# light_switch_smd.net
KiCad netlist of a schematic drawn in EAGLE
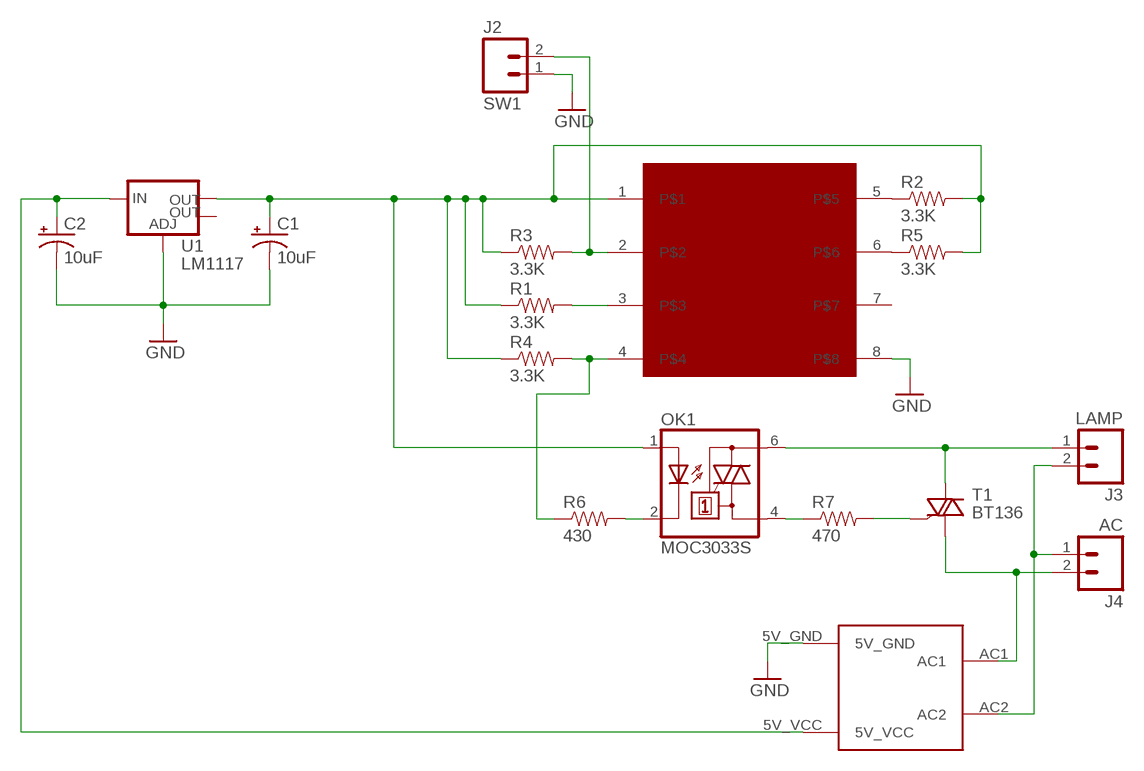
[diagram p0: schematic, sheet 1]

(export (version "E")
  (design (tool "Eeschema 10.0.6"))
  (components
    (comp (ref "C1")
      (value "10uF")
      (footprint "eagle-import:EIA3216")
      (libsource (lib "eagle-import") (part "10UF-16V-10%(TANT)"))
    )
    (comp (ref "C2")
      (value "10uF")
      (footprint "eagle-import:EIA3216")
      (libsource (lib "eagle-import") (part "10UF-16V-10%(TANT)"))
    )
    (comp (ref "J2")
      (value "SW1")
      (footprint "eagle-import:1X02_LONGPADS")
      (libsource (lib "eagle-import") (part "M02PTH3"))
    )
    (comp (ref "J3")
      (value "LAMP")
      (footprint "eagle-import:JST-2-PTH-VERT")
      (libsource (lib "eagle-import") (part "M02JST-PTH-VERT"))
    )
    (comp (ref "J4")
      (value "AC")
      (footprint "eagle-import:JST-2-PTH-VERT")
      (libsource (lib "eagle-import") (part "M02JST-PTH-VERT"))
    )
    (comp (ref "OK1")
      (value "MOC3033S")
      (footprint "eagle-import:DIL6-SMD")
      (fields (field (name "MF") "FAIRCHILD SEMICONDUCTOR") (field (name "MPN") "MOC3033S-M"))
      (libsource (lib "eagle-import") (part "MOC30S33"))
    )
    (comp (ref "R1")
      (value "3.3K")
      (footprint "eagle-import:1206")
      (libsource (lib "eagle-import") (part "RESISTOR1206"))
    )
    (comp (ref "R2")
      (value "3.3K")
      (footprint "eagle-import:1206")
      (libsource (lib "eagle-import") (part "RESISTOR1206"))
    )
    (comp (ref "R3")
      (value "3.3K")
      (footprint "eagle-import:1206")
      (libsource (lib "eagle-import") (part "RESISTOR1206"))
    )
    (comp (ref "R4")
      (value "3.3K")
      (footprint "eagle-import:1206")
      (libsource (lib "eagle-import") (part "RESISTOR1206"))
    )
    (comp (ref "R5")
      (value "3.3K")
      (footprint "eagle-import:1206")
      (libsource (lib "eagle-import") (part "RESISTOR1206"))
    )
    (comp (ref "R6")
      (value "430")
      (footprint "eagle-import:1206")
      (libsource (lib "eagle-import") (part "RESISTOR1206"))
    )
    (comp (ref "R7")
      (value "470")
      (footprint "eagle-import:1206")
      (libsource (lib "eagle-import") (part "RESISTOR1206"))
    )
    (comp (ref "T1")
      (value "BT136")
      (footprint "eagle-import:TO220AB")
      (libsource (lib "eagle-import") (part "BT136"))
    )
    (comp (ref "U$1")
      (value "HI-LINK5V-ACDC")
      (footprint "eagle-import:AC5V")
      (libsource (lib "eagle-import") (part "HI-LINK5V-ACDC"))
    )
    (comp (ref "U$2")
      (value "ESP8266-01")
      (footprint "eagle-import:ESP8266-01")
      (libsource (lib "eagle-import") (part "ESP8266-01"))
    )
    (comp (ref "U1")
      (value "LM1117")
      (footprint "eagle-import:SOT223")
      (libsource (lib "eagle-import") (part "V_REG_LM1117SOT223"))
    )
  )
  (nets
    (net (code "1") (name "GND") (class "Default")
      (node (ref "C1") (pin "C") (pinfunction "-_C") (pintype "passive"))
      (node (ref "C2") (pin "C") (pinfunction "-_C") (pintype "passive"))
      (node (ref "J2") (pin "1") (pinfunction "1_1") (pintype "passive"))
      (node (ref "U$1") (pin "5V_GND") (pinfunction "5V_GND_5V_GND") (pintype "bidirectional"))
      (node (ref "U$2") (pin "8") (pinfunction "P$8_8") (pintype "bidirectional"))
      (node (ref "U1") (pin "1") (pinfunction "ADJ_1") (pintype "input"))
    )
    (net (code "2") (name "Net-(C1-+)") (class "Default")
      (node (ref "C1") (pin "A") (pinfunction "+_A") (pintype "passive"))
      (node (ref "OK1") (pin "1") (pinfunction "A_1") (pintype "passive"))
      (node (ref "R1") (pin "1") (pinfunction "1_1") (pintype "passive"))
      (node (ref "R2") (pin "2") (pinfunction "2_2") (pintype "passive"))
      (node (ref "R3") (pin "1") (pinfunction "1_1") (pintype "passive"))
      (node (ref "R4") (pin "1") (pinfunction "1_1") (pintype "passive"))
      (node (ref "R5") (pin "2") (pinfunction "2_2") (pintype "passive"))
      (node (ref "U$2") (pin "1") (pinfunction "P$1_1") (pintype "bidirectional"))
      (node (ref "U1") (pin "2") (pinfunction "OUT_2") (pintype "output"))
    )
    (net (code "3") (name "Net-(C2-+)") (class "Default")
      (node (ref "C2") (pin "A") (pinfunction "+_A") (pintype "passive"))
      (node (ref "U$1") (pin "5V_VCC") (pinfunction "5V_VCC_5V_VCC") (pintype "bidirectional"))
      (node (ref "U1") (pin "3") (pinfunction "IN_3") (pintype "input"))
    )
    (net (code "4") (name "Net-(J3-Pad2)") (class "Default")
      (node (ref "J3") (pin "2") (pinfunction "2_2") (pintype "passive"))
      (node (ref "J4") (pin "1") (pinfunction "1_1") (pintype "passive"))
      (node (ref "U$1") (pin "AC2") (pinfunction "AC2_AC2") (pintype "bidirectional"))
    )
    (net (code "5") (name "Net-(OK1-A1)") (class "Default")
      (node (ref "OK1") (pin "4") (pinfunction "A1_4") (pintype "passive"))
      (node (ref "R7") (pin "1") (pinfunction "1_1") (pintype "passive"))
    )
    (net (code "6") (name "Net-(OK1-A2)") (class "Default")
      (node (ref "J3") (pin "1") (pinfunction "1_1") (pintype "passive"))
      (node (ref "OK1") (pin "6") (pinfunction "A2_6") (pintype "passive"))
      (node (ref "T1") (pin "2") (pinfunction "A2_2") (pintype "passive"))
    )
    (net (code "7") (name "Net-(OK1-C)") (class "Default")
      (node (ref "OK1") (pin "2") (pinfunction "C_2") (pintype "passive"))
      (node (ref "R6") (pin "2") (pinfunction "2_2") (pintype "passive"))
    )
    (net (code "8") (name "Net-(T1-A1)") (class "Default")
      (node (ref "J4") (pin "2") (pinfunction "2_2") (pintype "passive"))
      (node (ref "T1") (pin "1") (pinfunction "A1_1") (pintype "passive"))
      (node (ref "U$1") (pin "AC1") (pinfunction "AC1_AC1") (pintype "bidirectional"))
    )
    (net (code "9") (name "Net-(T1-G)") (class "Default")
      (node (ref "R7") (pin "2") (pinfunction "2_2") (pintype "passive"))
      (node (ref "T1") (pin "3") (pinfunction "G_3") (pintype "passive"))
    )
    (net (code "10") (name "Net-(U$2-P$2)") (class "Default")
      (node (ref "J2") (pin "2") (pinfunction "2_2") (pintype "passive"))
      (node (ref "R3") (pin "2") (pinfunction "2_2") (pintype "passive"))
      (node (ref "U$2") (pin "2") (pinfunction "P$2_2") (pintype "bidirectional"))
    )
    (net (code "11") (name "Net-(U$2-P$3)") (class "Default")
      (node (ref "R1") (pin "2") (pinfunction "2_2") (pintype "passive"))
      (node (ref "U$2") (pin "3") (pinfunction "P$3_3") (pintype "bidirectional"))
    )
    (net (code "12") (name "Net-(U$2-P$4)") (class "Default")
      (node (ref "R4") (pin "2") (pinfunction "2_2") (pintype "passive"))
      (node (ref "R6") (pin "1") (pinfunction "1_1") (pintype "passive"))
      (node (ref "U$2") (pin "4") (pinfunction "P$4_4") (pintype "bidirectional"))
    )
    (net (code "13") (name "Net-(U$2-P$5)") (class "Default")
      (node (ref "R2") (pin "1") (pinfunction "1_1") (pintype "passive"))
      (node (ref "U$2") (pin "5") (pinfunction "P$5_5") (pintype "bidirectional"))
    )
    (net (code "14") (name "Net-(U$2-P$6)") (class "Default")
      (node (ref "R5") (pin "1") (pinfunction "1_1") (pintype "passive"))
      (node (ref "U$2") (pin "6") (pinfunction "P$6_6") (pintype "bidirectional"))
    )
    (net (code "15") (name "unconnected-(U$2-P$7-Pad7)") (class "Default")
      (node (ref "U$2") (pin "7") (pinfunction "P$7_7") (pintype "bidirectional"))
    )
    (net (code "16") (name "unconnected-(U1-OUT-Pad4)") (class "Default")
      (node (ref "U1") (pin "4") (pinfunction "OUT_4") (pintype "output"))
    )
  )
)
